# Flipflop.net
KiCad netlist of a schematic drawn in EAGLE
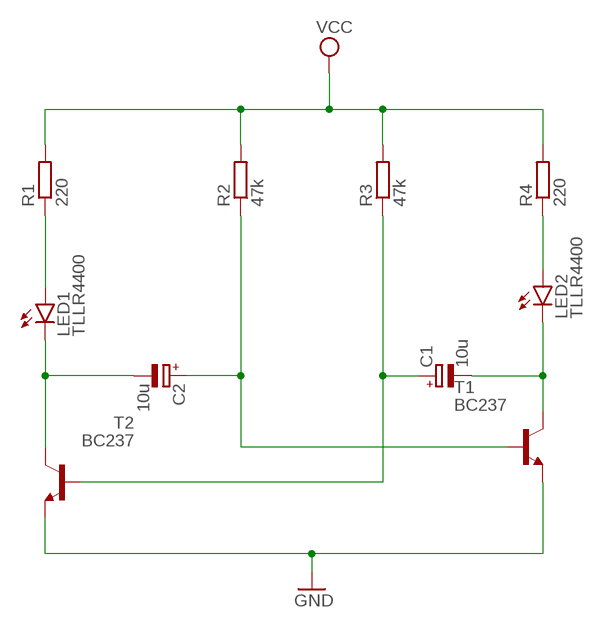
[diagram p0: schematic, sheet 1]

(export (version "E")
  (design (tool "Eeschema 10.0.6"))
  (components
    (comp (ref "C1")
      (value "10u")
      (footprint "eagle-import:140CLH-1014")
      (libsource (lib "eagle-import") (part "CPOL-EU140CLH-1014"))
    )
    (comp (ref "C2")
      (value "10u")
      (footprint "eagle-import:140CLH-1014")
      (libsource (lib "eagle-import") (part "CPOL-EU140CLH-1014"))
    )
    (comp (ref "LED1")
      (value "TLLR4400")
      (footprint "eagle-import:LED3MM")
      (fields (field (name "MF") "VISHAY SEMICONDUCTOR"))
      (libsource (lib "eagle-import") (part "TLLR4400"))
    )
    (comp (ref "LED2")
      (value "TLLR4400")
      (footprint "eagle-import:LED3MM")
      (fields (field (name "MF") "VISHAY SEMICONDUCTOR"))
      (libsource (lib "eagle-import") (part "TLLR4400"))
    )
    (comp (ref "R1")
      (value "220")
      (footprint "eagle-import:0207_12")
      (libsource (lib "eagle-import") (part "R-EU_0207/12"))
    )
    (comp (ref "R2")
      (value "47k")
      (footprint "eagle-import:0207_12")
      (libsource (lib "eagle-import") (part "R-EU_0207/12"))
    )
    (comp (ref "R3")
      (value "47k")
      (footprint "eagle-import:0207_12")
      (libsource (lib "eagle-import") (part "R-EU_0207/12"))
    )
    (comp (ref "R4")
      (value "220")
      (footprint "eagle-import:0207_12")
      (libsource (lib "eagle-import") (part "R-EU_0207/12"))
    )
    (comp (ref "T1")
      (value "BC237")
      (footprint "eagle-import:TO92")
      (libsource (lib "eagle-import") (part "BC237"))
    )
    (comp (ref "T2")
      (value "BC237")
      (footprint "eagle-import:TO92")
      (libsource (lib "eagle-import") (part "BC237"))
    )
  )
  (nets
    (net (code "1") (name "GND") (class "Default")
      (node (ref "T1") (pin "1") (pinfunction "E_1") (pintype "passive"))
      (node (ref "T2") (pin "1") (pinfunction "E_1") (pintype "passive"))
    )
    (net (code "2") (name "Net-(LED1-C)") (class "Default")
      (node (ref "C2") (pin "-") (pinfunction "-_-") (pintype "passive"))
      (node (ref "LED1") (pin "K") (pinfunction "C_K") (pintype "passive"))
      (node (ref "T2") (pin "3") (pinfunction "C_3") (pintype "passive"))
    )
    (net (code "3") (name "Net-(LED1-PadA)") (class "Default")
      (node (ref "LED1") (pin "A") (pinfunction "A_A") (pintype "passive"))
      (node (ref "R1") (pin "1") (pinfunction "1_1") (pintype "passive"))
    )
    (net (code "4") (name "Net-(LED2-C)") (class "Default")
      (node (ref "C1") (pin "-") (pinfunction "-_-") (pintype "passive"))
      (node (ref "LED2") (pin "K") (pinfunction "C_K") (pintype "passive"))
      (node (ref "T1") (pin "3") (pinfunction "C_3") (pintype "passive"))
    )
    (net (code "5") (name "Net-(LED2-PadA)") (class "Default")
      (node (ref "LED2") (pin "A") (pinfunction "A_A") (pintype "passive"))
      (node (ref "R4") (pin "1") (pinfunction "1_1") (pintype "passive"))
    )
    (net (code "6") (name "Net-(T1-B)") (class "Default")
      (node (ref "C2") (pin "+") (pinfunction "+_+") (pintype "passive"))
      (node (ref "R2") (pin "1") (pinfunction "1_1") (pintype "passive"))
      (node (ref "T1") (pin "2") (pinfunction "B_2") (pintype "passive"))
    )
    (net (code "7") (name "Net-(T2-B)") (class "Default")
      (node (ref "C1") (pin "+") (pinfunction "+_+") (pintype "passive"))
      (node (ref "R3") (pin "1") (pinfunction "1_1") (pintype "passive"))
      (node (ref "T2") (pin "2") (pinfunction "B_2") (pintype "passive"))
    )
    (net (code "8") (name "VCC") (class "Default")
      (node (ref "R1") (pin "2") (pinfunction "2_2") (pintype "passive"))
      (node (ref "R2") (pin "2") (pinfunction "2_2") (pintype "passive"))
      (node (ref "R3") (pin "2") (pinfunction "2_2") (pintype "passive"))
      (node (ref "R4") (pin "2") (pinfunction "2_2") (pintype "passive"))
    )
  )
)
